# 07_USB_Type-C_DFP_DP_ALT.net
KiCad netlist of a schematic drawn in Altium Designer
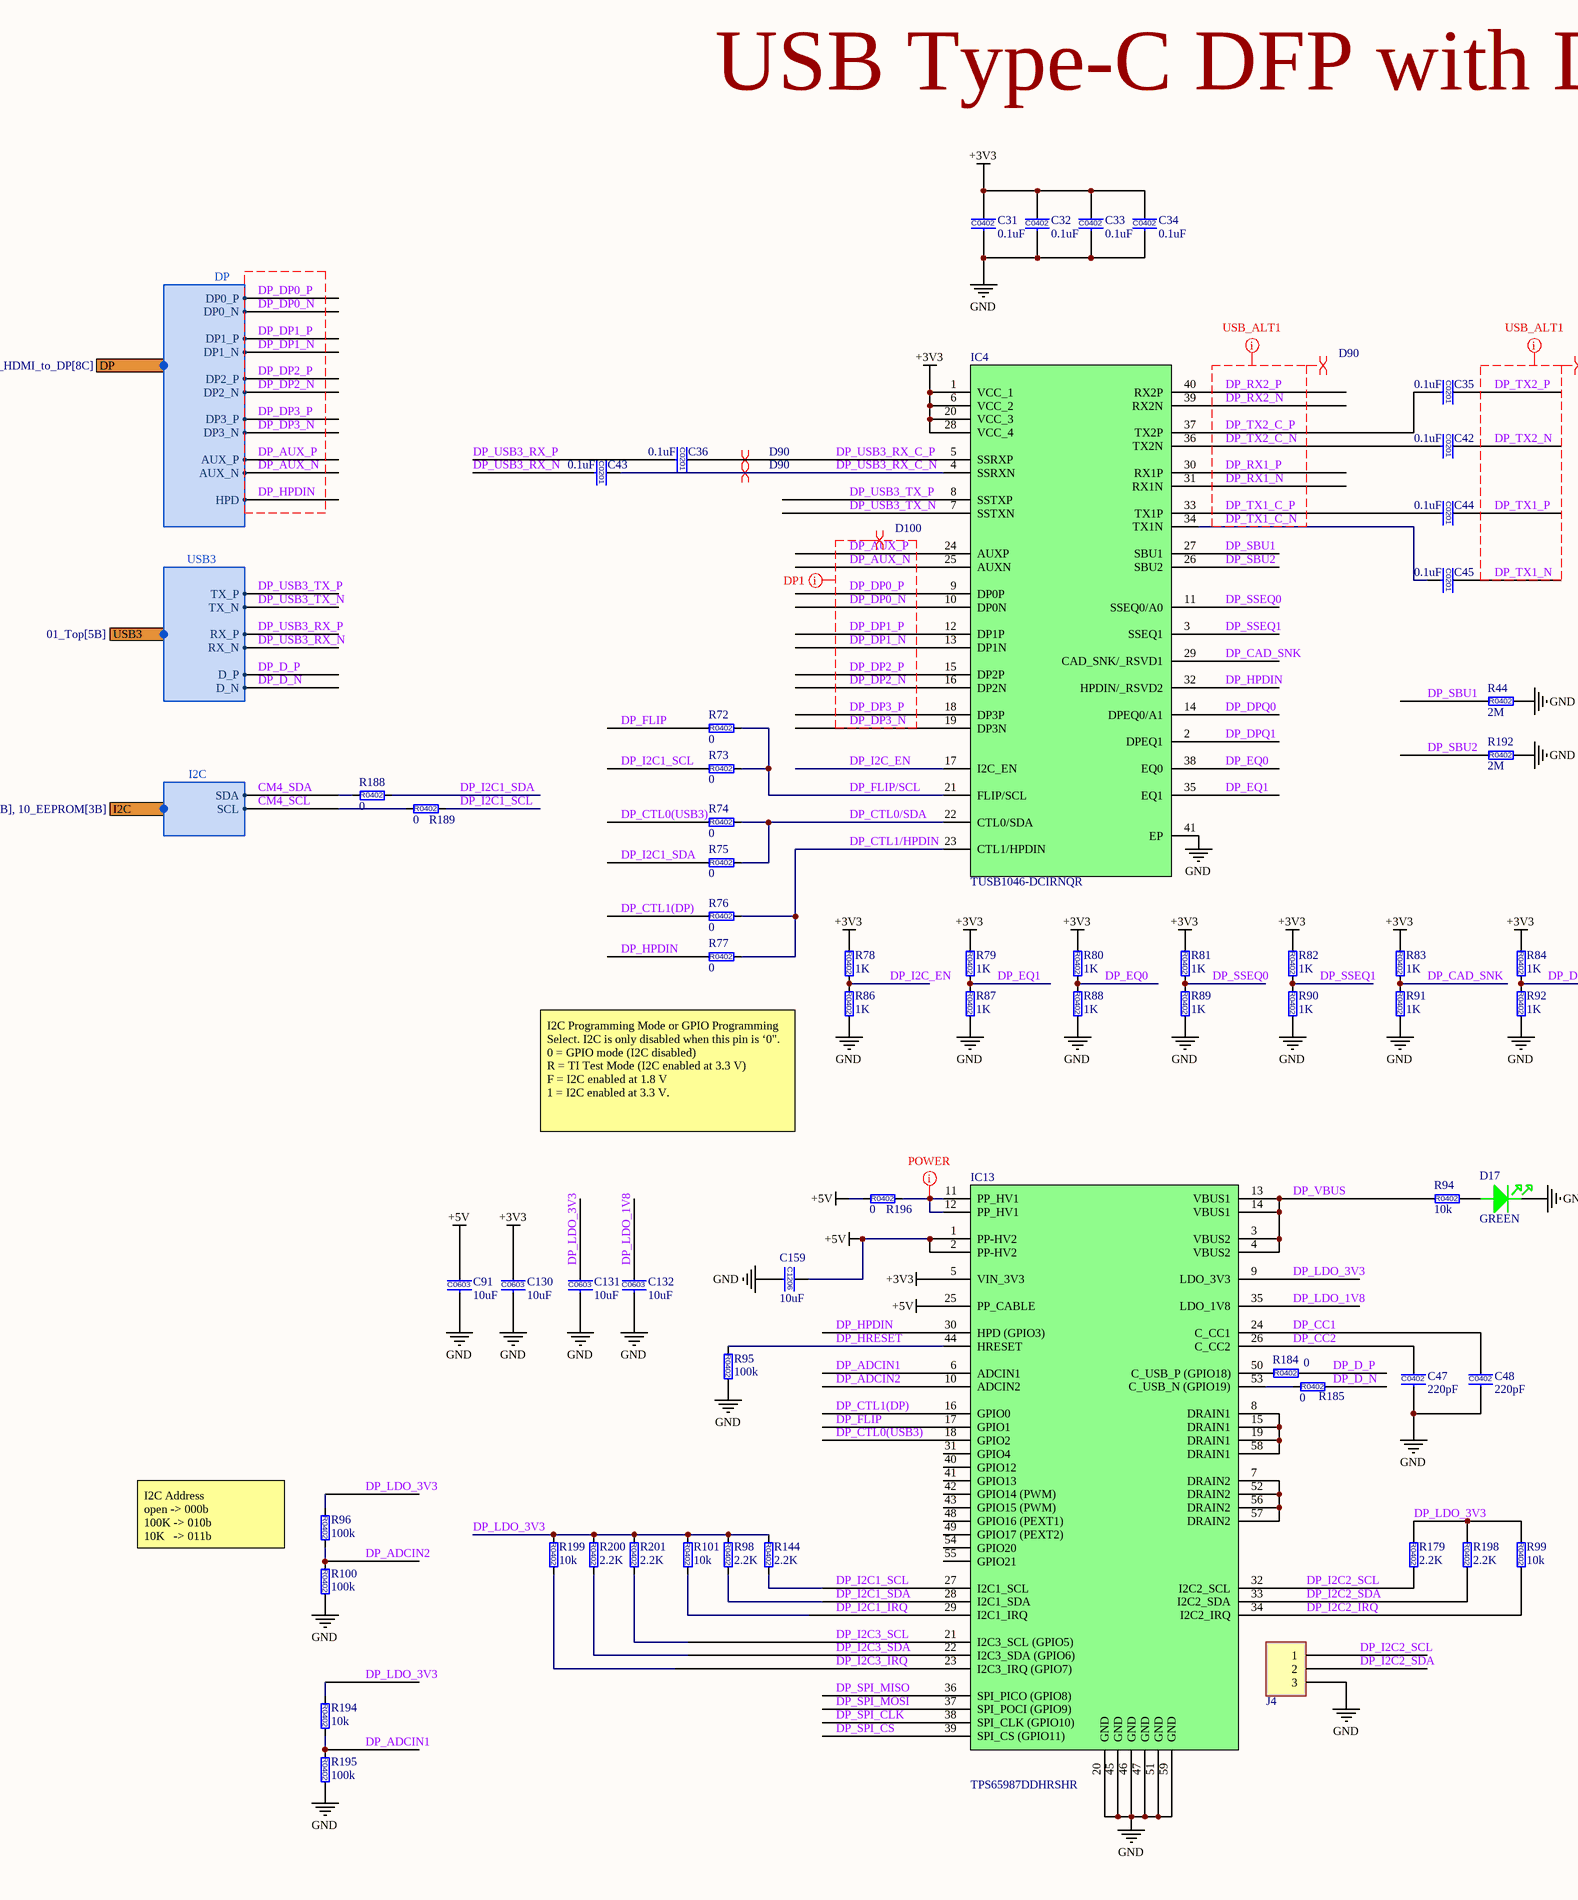
[diagram p0: 07_USB_Type-C_DFP_DP_ALT.SchDoc, left]
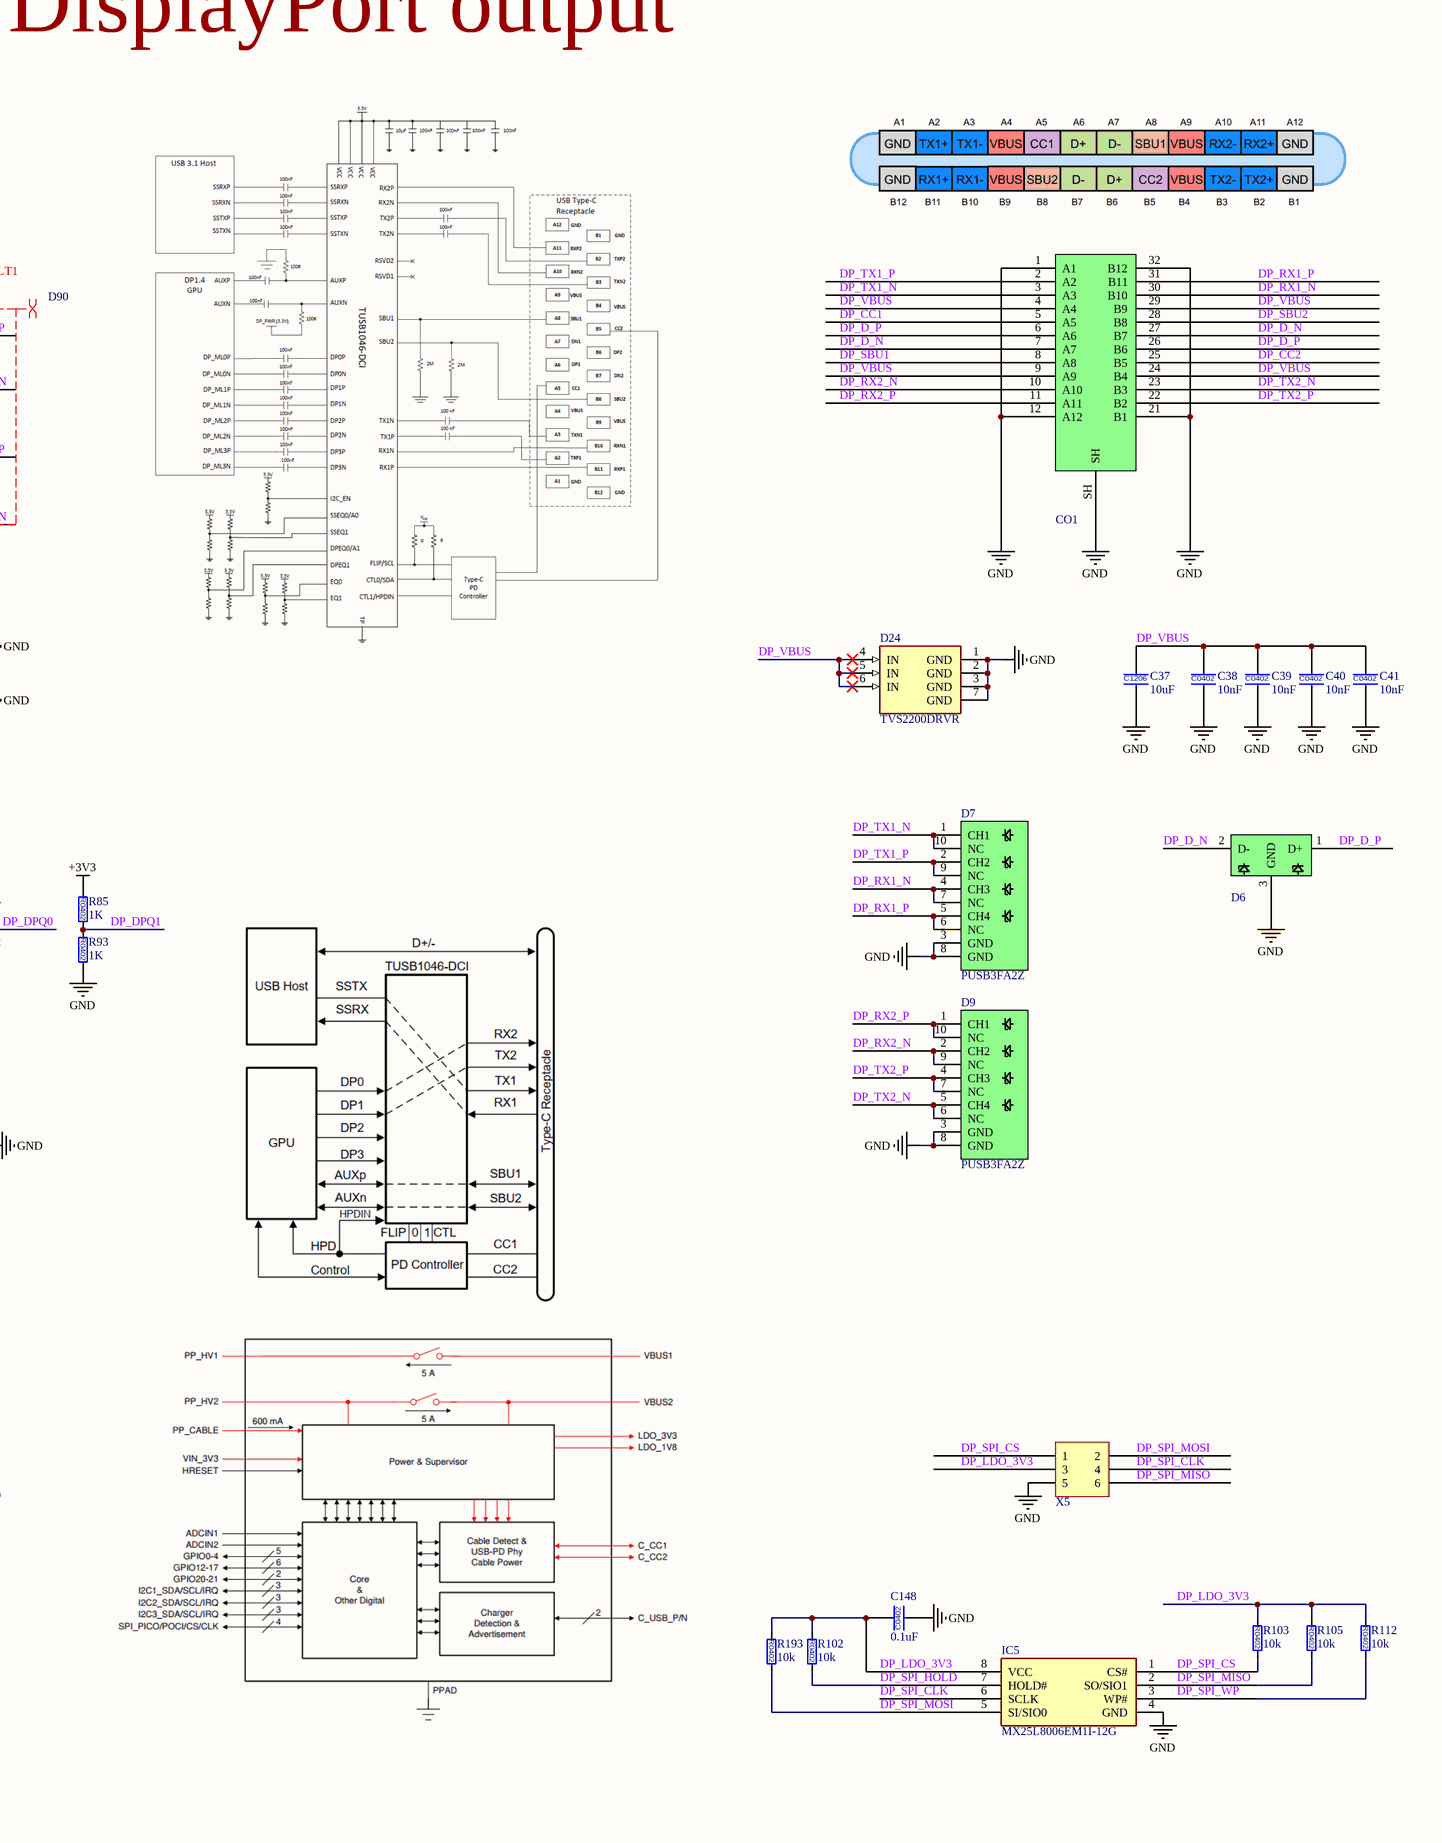
[diagram p1: 07_USB_Type-C_DFP_DP_ALT.SchDoc, right]

(export (version "E")
  (design (tool "Eeschema 10.0.6"))
  (components
    (comp (ref "C31")
      (value "0.1uF")
      (footprint "C0402")
      (description "CAP CER  0.1uF 10% 25V X5R 0402")
      (fields
        (field (name "MANUFACTURER") "AVX Corporation")
        (field (name "MANUFACTURER PART NUMBER") "04023D104KAT2A")
      )
      (libsource (lib "Capacitor") (part "04023D104KAT2A"))
    )
    (comp (ref "C32")
      (value "0.1uF")
      (footprint "C0402")
      (description "CAP CER  0.1uF 10% 25V X5R 0402")
      (fields
        (field (name "MANUFACTURER") "AVX Corporation")
        (field (name "MANUFACTURER PART NUMBER") "04023D104KAT2A")
      )
      (libsource (lib "Capacitor") (part "04023D104KAT2A"))
    )
    (comp (ref "C33")
      (value "0.1uF")
      (footprint "C0402")
      (description "CAP CER  0.1uF 10% 25V X5R 0402")
      (fields
        (field (name "MANUFACTURER") "AVX Corporation")
        (field (name "MANUFACTURER PART NUMBER") "04023D104KAT2A")
      )
      (libsource (lib "Capacitor") (part "04023D104KAT2A"))
    )
    (comp (ref "C34")
      (value "0.1uF")
      (footprint "C0402")
      (description "CAP CER  0.1uF 10% 25V X5R 0402")
      (fields
        (field (name "MANUFACTURER") "AVX Corporation")
        (field (name "MANUFACTURER PART NUMBER") "04023D104KAT2A")
      )
      (libsource (lib "Capacitor") (part "04023D104KAT2A"))
    )
    (comp (ref "C35")
      (value "0.1uF")
      (footprint "C0201")
      (description "CAP CER  0.1uF 10% 6.3V X5R 0201")
      (fields
        (field (name "MANUFACTURER") "AVX Corporation")
        (field (name "MANUFACTURER PART NUMBER") "02016D104KAT")
      )
      (libsource (lib "Capacitor") (part "02016D104KAT"))
    )
    (comp (ref "C36")
      (value "0.1uF")
      (footprint "C0201")
      (description "CAP CER  0.1uF 10% 6.3V X5R 0201")
      (fields
        (field (name "MANUFACTURER") "AVX Corporation")
        (field (name "MANUFACTURER PART NUMBER") "02016D104KAT")
      )
      (libsource (lib "Capacitor") (part "02016D104KAT"))
    )
    (comp (ref "C37")
      (value "10uF")
      (footprint "C1206")
      (description "CAP CER  10uF 10% 50V X5R 1206")
      (fields
        (field (name "MANUFACTURER") "KYOCERA AVX")
        (field (name "MANUFACTURER PART NUMBER") "12065D106KAT4A")
      )
      (libsource (lib "Capacitor") (part "12065D106KAT4A"))
    )
    (comp (ref "C38")
      (value "10nF")
      (footprint "C0402")
      (description "CAP CER 10nF 5% 50V X7R 0402")
      (fields
        (field (name "MANUFACTURER") "KYOCERA AVX")
        (field (name "MANUFACTURER PART NUMBER") "04025C103JAT2A")
      )
      (libsource (lib "Capacitor") (part "04025C103JAT2A"))
    )
    (comp (ref "C39")
      (value "10nF")
      (footprint "C0402")
      (description "CAP CER 10nF 5% 50V X7R 0402")
      (fields
        (field (name "MANUFACTURER") "KYOCERA AVX")
        (field (name "MANUFACTURER PART NUMBER") "04025C103JAT2A")
      )
      (libsource (lib "Capacitor") (part "04025C103JAT2A"))
    )
    (comp (ref "C40")
      (value "10nF")
      (footprint "C0402")
      (description "CAP CER 10nF 5% 50V X7R 0402")
      (fields
        (field (name "MANUFACTURER") "KYOCERA AVX")
        (field (name "MANUFACTURER PART NUMBER") "04025C103JAT2A")
      )
      (libsource (lib "Capacitor") (part "04025C103JAT2A"))
    )
    (comp (ref "C41")
      (value "10nF")
      (footprint "C0402")
      (description "CAP CER 10nF 5% 50V X7R 0402")
      (fields
        (field (name "MANUFACTURER") "KYOCERA AVX")
        (field (name "MANUFACTURER PART NUMBER") "04025C103JAT2A")
      )
      (libsource (lib "Capacitor") (part "04025C103JAT2A"))
    )
    (comp (ref "C42")
      (value "0.1uF")
      (footprint "C0201")
      (description "CAP CER  0.1uF 10% 6.3V X5R 0201")
      (fields
        (field (name "MANUFACTURER") "AVX Corporation")
        (field (name "MANUFACTURER PART NUMBER") "02016D104KAT")
      )
      (libsource (lib "Capacitor") (part "02016D104KAT"))
    )
    (comp (ref "C43")
      (value "0.1uF")
      (footprint "C0201")
      (description "CAP CER  0.1uF 10% 6.3V X5R 0201")
      (fields
        (field (name "MANUFACTURER") "AVX Corporation")
        (field (name "MANUFACTURER PART NUMBER") "02016D104KAT")
      )
      (libsource (lib "Capacitor") (part "02016D104KAT"))
    )
    (comp (ref "C44")
      (value "0.1uF")
      (footprint "C0201")
      (description "CAP CER  0.1uF 10% 6.3V X5R 0201")
      (fields
        (field (name "MANUFACTURER") "AVX Corporation")
        (field (name "MANUFACTURER PART NUMBER") "02016D104KAT")
      )
      (libsource (lib "Capacitor") (part "02016D104KAT"))
    )
    (comp (ref "C45")
      (value "0.1uF")
      (footprint "C0201")
      (description "CAP CER  0.1uF 10% 6.3V X5R 0201")
      (fields
        (field (name "MANUFACTURER") "AVX Corporation")
        (field (name "MANUFACTURER PART NUMBER") "02016D104KAT")
      )
      (libsource (lib "Capacitor") (part "02016D104KAT"))
    )
    (comp (ref "C47")
      (value "220pF")
      (footprint "C0402")
      (description "CAP CER  220pF 5% 25V NP0 0402")
      (fields
        (field (name "MANUFACTURER") "KYOCERA AVX")
        (field (name "MANUFACTURER PART NUMBER") "04023A221JAT4A")
      )
      (libsource (lib "Capacitor") (part "04023A221JAT4A"))
    )
    (comp (ref "C48")
      (value "220pF")
      (footprint "C0402")
      (description "CAP CER  220pF 5% 25V NP0 0402")
      (fields
        (field (name "MANUFACTURER") "KYOCERA AVX")
        (field (name "MANUFACTURER PART NUMBER") "04023A221JAT4A")
      )
      (libsource (lib "Capacitor") (part "04023A221JAT4A"))
    )
    (comp (ref "C91")
      (value "10uF")
      (footprint "C0603")
      (description "CAP CER 10uF 10% 10V X5R 0603")
      (fields
        (field (name "MANUFACTURER") "KYOCERA AVX")
        (field (name "MANUFACTURER PART NUMBER") "0603ZD106KAT2A")
      )
      (libsource (lib "Capacitor") (part "0603ZD106KAT2A"))
    )
    (comp (ref "C130")
      (value "10uF")
      (footprint "C0603")
      (description "CAP CER 10uF 10% 10V X5R 0603")
      (fields
        (field (name "MANUFACTURER") "KYOCERA AVX")
        (field (name "MANUFACTURER PART NUMBER") "0603ZD106KAT2A")
      )
      (libsource (lib "Capacitor") (part "0603ZD106KAT2A"))
    )
    (comp (ref "C131")
      (value "10uF")
      (footprint "C0603")
      (description "CAP CER 10uF 10% 10V X5R 0603")
      (fields
        (field (name "MANUFACTURER") "KYOCERA AVX")
        (field (name "MANUFACTURER PART NUMBER") "0603ZD106KAT2A")
      )
      (libsource (lib "Capacitor") (part "0603ZD106KAT2A"))
    )
    (comp (ref "C132")
      (value "10uF")
      (footprint "C0603")
      (description "CAP CER 10uF 10% 10V X5R 0603")
      (fields
        (field (name "MANUFACTURER") "KYOCERA AVX")
        (field (name "MANUFACTURER PART NUMBER") "0603ZD106KAT2A")
      )
      (libsource (lib "Capacitor") (part "0603ZD106KAT2A"))
    )
    (comp (ref "C148")
      (value "0.1uF")
      (footprint "C0402")
      (description "CAP CER  0.1uF 10% 25V X5R 0402")
      (fields
        (field (name "MANUFACTURER") "AVX Corporation")
        (field (name "MANUFACTURER PART NUMBER") "04023D104KAT2A")
      )
      (libsource (lib "Capacitor") (part "04023D104KAT2A"))
    )
    (comp (ref "C159")
      (value "10uF")
      (footprint "C1206")
      (description "CAP CER  10uF 10% 50V X5R 1206")
      (fields
        (field (name "MANUFACTURER") "KYOCERA AVX")
        (field (name "MANUFACTURER PART NUMBER") "12065D106KAT4A")
      )
      (libsource (lib "Capacitor") (part "12065D106KAT4A"))
    )
    (comp (ref "CO1")
      (value "USB4070-30-C")
      (footprint "USB4070-30-C")
      (description "24 Position 20 VDC USB Type C Horizontal USB 3.1 Receptacle Connector")
      (fields
        (field (name "PART NUMBER") "CO0021")
        (field (name "MANUFACTURER") "Global Connector Technology")
      )
      (libsource (lib "new") (part "USB4070-30-C"))
    )
    (comp (ref "D6")
      (value "TPD2EUSB30DRTR")
      (footprint "TPD2EUSB30DRTR_SOT-3")
      (fields (field (name "MANUFACTURER") "Texas Instruments"))
      (libsource (lib "new") (part "TPD2EUSB30DRTR"))
    )
    (comp (ref "D7")
      (value "PUSB3FA2Z")
      (footprint "PUSB3FA2Z_DFN_2510_10")
      (description "PUSB3FA2/SOT1176/XSON10")
      (fields (field (name "PART NUMBER") "DI0007") (field (name "MANUFACTURER") "Nexperia"))
      (libsource (lib "new") (part "PUSB3FA2Z"))
    )
    (comp (ref "D9")
      (value "PUSB3FA2Z")
      (footprint "PUSB3FA2Z_DFN_2510_10")
      (description "PUSB3FA2/SOT1176/XSON10")
      (fields (field (name "PART NUMBER") "DI0007") (field (name "MANUFACTURER") "Nexperia"))
      (libsource (lib "new") (part "PUSB3FA2Z"))
    )
    (comp (ref "D17")
      (value "GREEN")
      (footprint "LED_0603")
      (description "LED Uni-Color Yellow Green 574nm 2-Pin Chip 0603(1608Metric) T/R")
      (fields
        (field (name "MANUFACTURER") "Vishay Semiconductors")
        (field (name "MANUFACTURER PART NUMBER") "VLMG1300-GS08")
      )
      (libsource (lib "led") (part "LED_SMD_0603_GREEN"))
    )
    (comp (ref "D24")
      (value "TVS2200DRVR")
      (footprint "TVS2200D_SON_6")
      (description "22-V flat-clamp surge protection device 6-WSON -40 to 125")
      (fields
        (field (name "OCTOPART") "https://octopart.com/tvs2200drvr-texas+instruments-88217346")
        (field (name "MANUFACTURER") "Texas Instruments")
      )
      (libsource (lib "new") (part "TVS2200DRVR"))
    )
    (comp (ref "IC4")
      (value "TUSB1046-DCIRNQR")
      (footprint "TUSB1046_WQFN_40")
      (fields
        (field (name "MOUSER PART NUMBER") "595-TUSB1046-DCIRNQR")
        (field (name "MANUFACTURER") "Texas Instruments")
        (field (name "MANUFACTURER PART NUMBER") "TUSB1046AI-DCIRNQR")
      )
      (libsource (lib "new") (part "TUSB1046-DCIRNQR"))
    )
    (comp (ref "IC5")
      (value "MX25L8006EM1I-12G")
      (footprint "SamacSys:SOIC127P600X175-8N")
      (description "NOR Flash Serial 3.3V 8M-bit 8M/4M x 1/2-bit 8ns 8-Pin SOP / IC FLASH 8MBIT 86MHZ 8SOP")
      (fields (field (name "MANUFACTURER") "Macronix"))
      (libsource (lib "new") (part "MX25L8006EM1I-12G"))
    )
    (comp (ref "IC13")
      (value "TPS65987DDHRSHR")
      (footprint "TPS65987D_VQFN-56")
      (description "USB Type-C™ and USB PD controller with integrated power switches 56-VQFN -10 to 75")
      (fields (field (name "PART NUMBER") "IC0052") (field (name "MANUFACTURER") "Texas Instruments"))
      (libsource (lib "new") (part "TPS65987DDHRSHR"))
    )
    (comp (ref "J4")
      (value "PLS-3")
      (footprint "PLS-3-3D")
      (description "Board to Board Connector Straight Header Single Row 3 Position 2.54mm Pitch Through Hole Bag")
      (fields
        (field (name "MANUFACTURER") "Amphenol")
        (field (name "MANUFACTURER PART NUMBER") "G800W305018EU")
      )
      (libsource (lib "Connector") (part "PLS-3"))
    )
    (comp (ref "R44")
      (value "2M")
      (footprint "R0402")
      (description "RES SMD 2M ohm 1% 1/16W R0402")
      (fields
        (field (name "MANUFACTURER") "Vishay")
        (field (name "MANUFACTURER PART NUMBER") "CRCW04022M00FKEDC")
      )
      (libsource (lib "Resistor") (part "CRCW04022M00FKEDC"))
    )
    (comp (ref "R72")
      (value "0")
      (footprint "R0402")
      (description "RES SMD 0 ohm 1/16W R0402")
      (fields
        (field (name "MANUFACTURER") "Vishay Dale")
        (field (name "MANUFACTURER PART NUMBER") "CRCW04020000Z0")
      )
      (libsource (lib "Resistor") (part "CRCW04020000Z0"))
    )
    (comp (ref "R73")
      (value "0")
      (footprint "R0402")
      (description "RES SMD 0 ohm 1/16W R0402")
      (fields
        (field (name "MANUFACTURER") "Vishay Dale")
        (field (name "MANUFACTURER PART NUMBER") "CRCW04020000Z0")
      )
      (libsource (lib "Resistor") (part "CRCW04020000Z0"))
    )
    (comp (ref "R74")
      (value "0")
      (footprint "R0402")
      (description "RES SMD 0 ohm 1/16W R0402")
      (fields
        (field (name "MANUFACTURER") "Vishay Dale")
        (field (name "MANUFACTURER PART NUMBER") "CRCW04020000Z0")
      )
      (libsource (lib "Resistor") (part "CRCW04020000Z0"))
    )
    (comp (ref "R75")
      (value "0")
      (footprint "R0402")
      (description "RES SMD 0 ohm 1/16W R0402")
      (fields
        (field (name "MANUFACTURER") "Vishay Dale")
        (field (name "MANUFACTURER PART NUMBER") "CRCW04020000Z0")
      )
      (libsource (lib "Resistor") (part "CRCW04020000Z0"))
    )
    (comp (ref "R76")
      (value "0")
      (footprint "R0402")
      (description "RES SMD 0 ohm 1/16W R0402")
      (fields
        (field (name "MANUFACTURER") "Vishay Dale")
        (field (name "MANUFACTURER PART NUMBER") "CRCW04020000Z0")
      )
      (libsource (lib "Resistor") (part "CRCW04020000Z0"))
    )
    (comp (ref "R77")
      (value "0")
      (footprint "R0402")
      (description "RES SMD 0 ohm 1/16W R0402")
      (fields
        (field (name "MANUFACTURER") "Vishay Dale")
        (field (name "MANUFACTURER PART NUMBER") "CRCW04020000Z0")
      )
      (libsource (lib "Resistor") (part "CRCW04020000Z0"))
    )
    (comp (ref "R78")
      (value "1K")
      (footprint "R0402")
      (description "RES SMD 1K ohm 1% 1/16W R0402")
      (fields
        (field (name "MANUFACTURER") "Vishay")
        (field (name "MANUFACTURER PART NUMBER") "CRCW04021K00FKEDC")
      )
      (libsource (lib "Resistor") (part "CRCW04021K00FKEDC"))
    )
    (comp (ref "R79")
      (value "1K")
      (footprint "R0402")
      (description "RES SMD 1K ohm 1% 1/16W R0402")
      (fields
        (field (name "MANUFACTURER") "Vishay")
        (field (name "MANUFACTURER PART NUMBER") "CRCW04021K00FKEDC")
      )
      (libsource (lib "Resistor") (part "CRCW04021K00FKEDC"))
    )
    (comp (ref "R80")
      (value "1K")
      (footprint "R0402")
      (description "RES SMD 1K ohm 1% 1/16W R0402")
      (fields
        (field (name "MANUFACTURER") "Vishay")
        (field (name "MANUFACTURER PART NUMBER") "CRCW04021K00FKEDC")
      )
      (libsource (lib "Resistor") (part "CRCW04021K00FKEDC"))
    )
    (comp (ref "R81")
      (value "1K")
      (footprint "R0402")
      (description "RES SMD 1K ohm 1% 1/16W R0402")
      (fields
        (field (name "MANUFACTURER") "Vishay")
        (field (name "MANUFACTURER PART NUMBER") "CRCW04021K00FKEDC")
      )
      (libsource (lib "Resistor") (part "CRCW04021K00FKEDC"))
    )
    (comp (ref "R82")
      (value "1K")
      (footprint "R0402")
      (description "RES SMD 1K ohm 1% 1/16W R0402")
      (fields
        (field (name "MANUFACTURER") "Vishay")
        (field (name "MANUFACTURER PART NUMBER") "CRCW04021K00FKEDC")
      )
      (libsource (lib "Resistor") (part "CRCW04021K00FKEDC"))
    )
    (comp (ref "R83")
      (value "1K")
      (footprint "R0402")
      (description "RES SMD 1K ohm 1% 1/16W R0402")
      (fields
        (field (name "MANUFACTURER") "Vishay")
        (field (name "MANUFACTURER PART NUMBER") "CRCW04021K00FKEDC")
      )
      (libsource (lib "Resistor") (part "CRCW04021K00FKEDC"))
    )
    (comp (ref "R84")
      (value "1K")
      (footprint "R0402")
      (description "RES SMD 1K ohm 1% 1/16W R0402")
      (fields
        (field (name "MANUFACTURER") "Vishay")
        (field (name "MANUFACTURER PART NUMBER") "CRCW04021K00FKEDC")
      )
      (libsource (lib "Resistor") (part "CRCW04021K00FKEDC"))
    )
    (comp (ref "R85")
      (value "1K")
      (footprint "R0402")
      (description "RES SMD 1K ohm 1% 1/16W R0402")
      (fields
        (field (name "MANUFACTURER") "Vishay")
        (field (name "MANUFACTURER PART NUMBER") "CRCW04021K00FKEDC")
      )
      (libsource (lib "Resistor") (part "CRCW04021K00FKEDC"))
    )
    (comp (ref "R86")
      (value "1K")
      (footprint "R0402")
      (description "RES SMD 1K ohm 1% 1/16W R0402")
      (fields
        (field (name "MANUFACTURER") "Vishay")
        (field (name "MANUFACTURER PART NUMBER") "CRCW04021K00FKEDC")
      )
      (libsource (lib "Resistor") (part "CRCW04021K00FKEDC"))
    )
    (comp (ref "R87")
      (value "1K")
      (footprint "R0402")
      (description "RES SMD 1K ohm 1% 1/16W R0402")
      (fields
        (field (name "MANUFACTURER") "Vishay")
        (field (name "MANUFACTURER PART NUMBER") "CRCW04021K00FKEDC")
      )
      (libsource (lib "Resistor") (part "CRCW04021K00FKEDC"))
    )
    (comp (ref "R88")
      (value "1K")
      (footprint "R0402")
      (description "RES SMD 1K ohm 1% 1/16W R0402")
      (fields
        (field (name "MANUFACTURER") "Vishay")
        (field (name "MANUFACTURER PART NUMBER") "CRCW04021K00FKEDC")
      )
      (libsource (lib "Resistor") (part "CRCW04021K00FKEDC"))
    )
    (comp (ref "R89")
      (value "1K")
      (footprint "R0402")
      (description "RES SMD 1K ohm 1% 1/16W R0402")
      (fields
        (field (name "MANUFACTURER") "Vishay")
        (field (name "MANUFACTURER PART NUMBER") "CRCW04021K00FKEDC")
      )
      (libsource (lib "Resistor") (part "CRCW04021K00FKEDC"))
    )
    (comp (ref "R90")
      (value "1K")
      (footprint "R0402")
      (description "RES SMD 1K ohm 1% 1/16W R0402")
      (fields
        (field (name "MANUFACTURER") "Vishay")
        (field (name "MANUFACTURER PART NUMBER") "CRCW04021K00FKEDC")
      )
      (libsource (lib "Resistor") (part "CRCW04021K00FKEDC"))
    )
    (comp (ref "R91")
      (value "1K")
      (footprint "R0402")
      (description "RES SMD 1K ohm 1% 1/16W R0402")
      (fields
        (field (name "MANUFACTURER") "Vishay")
        (field (name "MANUFACTURER PART NUMBER") "CRCW04021K00FKEDC")
      )
      (libsource (lib "Resistor") (part "CRCW04021K00FKEDC"))
    )
    (comp (ref "R92")
      (value "1K")
      (footprint "R0402")
      (description "RES SMD 1K ohm 1% 1/16W R0402")
      (fields
        (field (name "MANUFACTURER") "Vishay")
        (field (name "MANUFACTURER PART NUMBER") "CRCW04021K00FKEDC")
      )
      (libsource (lib "Resistor") (part "CRCW04021K00FKEDC"))
    )
    (comp (ref "R93")
      (value "1K")
      (footprint "R0402")
      (description "RES SMD 1K ohm 1% 1/16W R0402")
      (fields
        (field (name "MANUFACTURER") "Vishay")
        (field (name "MANUFACTURER PART NUMBER") "CRCW04021K00FKEDC")
      )
      (libsource (lib "Resistor") (part "CRCW04021K00FKEDC"))
    )
    (comp (ref "R94")
      (value "10k")
      (footprint "R0402")
      (description "RES SMD 10K ohm 1% 1/16W R0402")
      (fields
        (field (name "MANUFACTURER") "Vishay")
        (field (name "MANUFACTURER PART NUMBER") "CRCW040210K0FK")
      )
      (libsource (lib "Resistor") (part "CRCW040210K0FK"))
    )
    (comp (ref "R95")
      (value "100k")
      (footprint "R0402")
      (description "RES SMD 100K ohm 1% 1/16W R0402")
      (fields
        (field (name "MANUFACTURER") "Vishay")
        (field (name "MANUFACTURER PART NUMBER") "CRCW0402100KFKEDC")
      )
      (libsource (lib "Resistor") (part "CRCW0402100KFKEDC"))
    )
    (comp (ref "R96")
      (value "100k")
      (footprint "R0402")
      (description "RES SMD 100K ohm 1% 1/16W R0402")
      (fields
        (field (name "MANUFACTURER") "Vishay")
        (field (name "MANUFACTURER PART NUMBER") "CRCW0402100KFKEDC")
      )
      (libsource (lib "Resistor") (part "CRCW0402100KFKEDC"))
    )
    (comp (ref "R98")
      (value "2.2K")
      (footprint "R0402")
      (description "RES SMD 2.2K ohm 1% 1/16W R0402")
      (fields
        (field (name "MANUFACTURER") "Vishay")
        (field (name "MANUFACTURER PART NUMBER") "CRCW04022K20FK")
      )
      (libsource (lib "Resistor") (part "CRCW04022K20FK"))
    )
    (comp (ref "R99")
      (value "10k")
      (footprint "R0402")
      (description "RES SMD 10K ohm 1% 1/16W R0402")
      (fields
        (field (name "MANUFACTURER") "Vishay")
        (field (name "MANUFACTURER PART NUMBER") "CRCW040210K0FK")
      )
      (libsource (lib "Resistor") (part "CRCW040210K0FK"))
    )
    (comp (ref "R100")
      (value "100k")
      (footprint "R0402")
      (description "RES SMD 100K ohm 1% 1/16W R0402")
      (fields
        (field (name "MANUFACTURER") "Vishay")
        (field (name "MANUFACTURER PART NUMBER") "CRCW0402100KFKEDC")
      )
      (libsource (lib "Resistor") (part "CRCW0402100KFKEDC"))
    )
    (comp (ref "R101")
      (value "10k")
      (footprint "R0402")
      (description "RES SMD 10K ohm 1% 1/16W R0402")
      (fields
        (field (name "MANUFACTURER") "Vishay")
        (field (name "MANUFACTURER PART NUMBER") "CRCW040210K0FK")
      )
      (libsource (lib "Resistor") (part "CRCW040210K0FK"))
    )
    (comp (ref "R102")
      (value "10k")
      (footprint "R0402")
      (description "RES SMD 10K ohm 1% 1/16W R0402")
      (fields
        (field (name "MANUFACTURER") "Vishay Dale")
        (field (name "MANUFACTURER PART NUMBER") "CRCW040210K0FK")
      )
      (libsource (lib "Resistor") (part "CRCW040210K0FK"))
    )
    (comp (ref "R103")
      (value "10k")
      (footprint "R0402")
      (description "RES SMD 10K ohm 1% 1/16W R0402")
      (fields
        (field (name "MANUFACTURER") "Vishay Dale")
        (field (name "MANUFACTURER PART NUMBER") "CRCW040210K0FK")
      )
      (libsource (lib "Resistor") (part "CRCW040210K0FK"))
    )
    (comp (ref "R105")
      (value "10k")
      (footprint "R0402")
      (description "RES SMD 10K ohm 1% 1/16W R0402")
      (fields
        (field (name "MANUFACTURER") "Vishay Dale")
        (field (name "MANUFACTURER PART NUMBER") "CRCW040210K0FK")
      )
      (libsource (lib "Resistor") (part "CRCW040210K0FK"))
    )
    (comp (ref "R112")
      (value "10k")
      (footprint "R0402")
      (description "RES SMD 10K ohm 1% 1/16W R0402")
      (fields
        (field (name "MANUFACTURER") "Vishay Dale")
        (field (name "MANUFACTURER PART NUMBER") "CRCW040210K0FK")
      )
      (libsource (lib "Resistor") (part "CRCW040210K0FK"))
    )
    (comp (ref "R144")
      (value "2.2K")
      (footprint "R0402")
      (description "RES SMD 2.2K ohm 1% 1/16W R0402")
      (fields
        (field (name "MANUFACTURER") "Vishay")
        (field (name "MANUFACTURER PART NUMBER") "CRCW04022K20FK")
      )
      (libsource (lib "Resistor") (part "CRCW04022K20FK"))
    )
    (comp (ref "R179")
      (value "2.2K")
      (footprint "R0402")
      (description "RES SMD 2.2K ohm 1% 1/16W R0402")
      (fields
        (field (name "MANUFACTURER") "Vishay")
        (field (name "MANUFACTURER PART NUMBER") "CRCW04022K20FK")
      )
      (libsource (lib "Resistor") (part "CRCW04022K20FK"))
    )
    (comp (ref "R184")
      (value "0")
      (footprint "R0402")
      (description "RES SMD 0 ohm 1/16W R0402")
      (fields
        (field (name "MANUFACTURER") "Vishay Dale")
        (field (name "MANUFACTURER PART NUMBER") "CRCW04020000Z0")
      )
      (libsource (lib "Resistor") (part "CRCW04020000Z0"))
    )
    (comp (ref "R185")
      (value "0")
      (footprint "R0402")
      (description "RES SMD 0 ohm 1/16W R0402")
      (fields
        (field (name "MANUFACTURER") "Vishay Dale")
        (field (name "MANUFACTURER PART NUMBER") "CRCW04020000Z0")
      )
      (libsource (lib "Resistor") (part "CRCW04020000Z0"))
    )
    (comp (ref "R188")
      (value "0")
      (footprint "R0402")
      (description "RES SMD 0 ohm 1/16W R0402")
      (fields
        (field (name "MANUFACTURER") "Vishay Dale")
        (field (name "MANUFACTURER PART NUMBER") "CRCW04020000Z0")
      )
      (libsource (lib "Resistor") (part "CRCW04020000Z0"))
    )
    (comp (ref "R189")
      (value "0")
      (footprint "R0402")
      (description "RES SMD 0 ohm 1/16W R0402")
      (fields
        (field (name "MANUFACTURER") "Vishay Dale")
        (field (name "MANUFACTURER PART NUMBER") "CRCW04020000Z0")
      )
      (libsource (lib "Resistor") (part "CRCW04020000Z0"))
    )
    (comp (ref "R192")
      (value "2M")
      (footprint "R0402")
      (description "RES SMD 2M ohm 1% 1/16W R0402")
      (fields
        (field (name "MANUFACTURER") "Vishay")
        (field (name "MANUFACTURER PART NUMBER") "CRCW04022M00FKEDC")
      )
      (libsource (lib "Resistor") (part "CRCW04022M00FKEDC"))
    )
    (comp (ref "R193")
      (value "10k")
      (footprint "R0402")
      (description "RES SMD 10K ohm 1% 1/16W R0402")
      (fields
        (field (name "MANUFACTURER") "Vishay Dale")
        (field (name "MANUFACTURER PART NUMBER") "CRCW040210K0FK")
      )
      (libsource (lib "Resistor") (part "CRCW040210K0FK"))
    )
    (comp (ref "R194")
      (value "10k")
      (footprint "R0402")
      (description "RES SMD 10K ohm 1% 1/16W R0402")
      (fields
        (field (name "MANUFACTURER") "Vishay")
        (field (name "MANUFACTURER PART NUMBER") "CRCW040210K0FK")
      )
      (libsource (lib "Resistor") (part "CRCW040210K0FK"))
    )
    (comp (ref "R195")
      (value "100k")
      (footprint "R0402")
      (description "RES SMD 100K ohm 1% 1/16W R0402")
      (fields
        (field (name "MANUFACTURER") "Vishay")
        (field (name "MANUFACTURER PART NUMBER") "CRCW0402100KFKEDC")
      )
      (libsource (lib "Resistor") (part "CRCW0402100KFKEDC"))
    )
    (comp (ref "R196")
      (value "0")
      (footprint "R0402")
      (description "RES SMD 0 ohm 1/16W R0402")
      (fields
        (field (name "MANUFACTURER") "Vishay Dale")
        (field (name "MANUFACTURER PART NUMBER") "CRCW04020000Z0")
      )
      (libsource (lib "Resistor") (part "CRCW04020000Z0"))
    )
    (comp (ref "R198")
      (value "2.2K")
      (footprint "R0402")
      (description "RES SMD 2.2K ohm 1% 1/16W R0402")
      (fields
        (field (name "MANUFACTURER") "Vishay")
        (field (name "MANUFACTURER PART NUMBER") "CRCW04022K20FK")
      )
      (libsource (lib "Resistor") (part "CRCW04022K20FK"))
    )
    (comp (ref "R199")
      (value "10k")
      (footprint "R0402")
      (description "RES SMD 10K ohm 1% 1/16W R0402")
      (fields
        (field (name "MANUFACTURER") "Vishay")
        (field (name "MANUFACTURER PART NUMBER") "CRCW040210K0FK")
      )
      (libsource (lib "Resistor") (part "CRCW040210K0FK"))
    )
    (comp (ref "R200")
      (value "2.2K")
      (footprint "R0402")
      (description "RES SMD 2.2K ohm 1% 1/16W R0402")
      (fields
        (field (name "MANUFACTURER") "Vishay")
        (field (name "MANUFACTURER PART NUMBER") "CRCW04022K20FK")
      )
      (libsource (lib "Resistor") (part "CRCW04022K20FK"))
    )
    (comp (ref "R201")
      (value "2.2K")
      (footprint "R0402")
      (description "RES SMD 2.2K ohm 1% 1/16W R0402")
      (fields
        (field (name "MANUFACTURER") "Vishay")
        (field (name "MANUFACTURER PART NUMBER") "CRCW04022K20FK")
      )
      (libsource (lib "Resistor") (part "CRCW04022K20FK"))
    )
    (comp (ref "X5")
      (value "PBD-6")
      (footprint "PXD-6")
      (description "Conn Unshrouded Header HDR 6 POS 2.54mm Solder ST Thru-Hole Poly Bag")
      (fields
        (field (name "MANUFACTURER") "Amphenol ICC / FCI")
        (field (name "MANUFACTURER PART NUMBER") "10076801-101-06LF")
        (field (name "PUBLISHER") "Altium Limited")
      )
      (libsource (lib "Connector") (part "PBD-6"))
    )
  )
  (nets
    (net (code "4") (name "+3V3") (class "Default")
      (node (ref "C130") (pin "1") (pinfunction "1_1") (pintype "passive"))
      (node (ref "C31") (pin "1") (pinfunction "1_1") (pintype "passive"))
      (node (ref "C32") (pin "1") (pinfunction "1_1") (pintype "passive"))
      (node (ref "C33") (pin "1") (pinfunction "1_1") (pintype "passive"))
      (node (ref "C34") (pin "1") (pinfunction "1_1") (pintype "passive"))
      (node (ref "IC13") (pin "5") (pinfunction "VIN_3V3_5") (pintype "passive"))
      (node (ref "IC4") (pin "1") (pinfunction "VCC_1_1") (pintype "passive"))
      (node (ref "IC4") (pin "20") (pinfunction "VCC_3_20") (pintype "passive"))
      (node (ref "IC4") (pin "28") (pinfunction "VCC_4_28") (pintype "passive"))
      (node (ref "IC4") (pin "6") (pinfunction "VCC_2_6") (pintype "passive"))
      (node (ref "R78") (pin "1") (pinfunction "1_1") (pintype "passive"))
      (node (ref "R79") (pin "1") (pinfunction "1_1") (pintype "passive"))
      (node (ref "R80") (pin "1") (pinfunction "1_1") (pintype "passive"))
      (node (ref "R81") (pin "1") (pinfunction "1_1") (pintype "passive"))
      (node (ref "R82") (pin "1") (pinfunction "1_1") (pintype "passive"))
      (node (ref "R83") (pin "1") (pinfunction "1_1") (pintype "passive"))
      (node (ref "R84") (pin "1") (pinfunction "1_1") (pintype "passive"))
      (node (ref "R85") (pin "1") (pinfunction "1_1") (pintype "passive"))
    )
    (net (code "5") (name "+5V") (class "Default")
      (node (ref "C159") (pin "1") (pinfunction "1_1") (pintype "passive"))
      (node (ref "C91") (pin "1") (pinfunction "1_1") (pintype "passive"))
      (node (ref "IC13") (pin "1") (pinfunction "PP-HV2_1") (pintype "passive"))
      (node (ref "IC13") (pin "2") (pinfunction "PP-HV2_2") (pintype "passive"))
      (node (ref "IC13") (pin "25") (pinfunction "PP_CABLE_25") (pintype "passive"))
      (node (ref "R196") (pin "1") (pinfunction "1_1") (pintype "passive"))
    )
    (net (code "6") (name "/CM4_SCL") (class "Default")
      (node (ref "R189") (pin "1") (pinfunction "1_1") (pintype "passive"))
    )
    (net (code "7") (name "/CM4_SDA") (class "Default")
      (node (ref "R188") (pin "1") (pinfunction "1_1") (pintype "passive"))
    )
    (net (code "8") (name "/DP_ADCIN1") (class "Default")
      (node (ref "IC13") (pin "6") (pinfunction "ADCIN1_6") (pintype "passive"))
      (node (ref "R194") (pin "2") (pinfunction "2_2") (pintype "passive"))
      (node (ref "R195") (pin "1") (pinfunction "1_1") (pintype "passive"))
    )
    (net (code "9") (name "/DP_ADCIN2") (class "Default")
      (node (ref "IC13") (pin "10") (pinfunction "ADCIN2_10") (pintype "passive"))
      (node (ref "R100") (pin "1") (pinfunction "1_1") (pintype "passive"))
      (node (ref "R96") (pin "2") (pinfunction "2_2") (pintype "passive"))
    )
    (net (code "10") (name "/DP_AUX_N") (class "Default")
      (node (ref "IC4") (pin "25") (pinfunction "AUXN_25") (pintype "passive"))
    )
    (net (code "11") (name "/DP_AUX_P") (class "Default")
      (node (ref "IC4") (pin "24") (pinfunction "AUXP_24") (pintype "passive"))
    )
    (net (code "12") (name "/DP_CAD_SNK") (class "Default")
      (node (ref "IC4") (pin "29") (pinfunction "CAD_SNK/_RSVD1_29") (pintype "passive"))
      (node (ref "R83") (pin "2") (pinfunction "2_2") (pintype "passive"))
      (node (ref "R91") (pin "1") (pinfunction "1_1") (pintype "passive"))
    )
    (net (code "13") (name "/DP_CC1") (class "Default")
      (node (ref "C48") (pin "1") (pinfunction "1_1") (pintype "passive"))
      (node (ref "CO1") (pin "5") (pinfunction "A5_5") (pintype "passive"))
      (node (ref "IC13") (pin "24") (pinfunction "C_CC1_24") (pintype "passive"))
    )
    (net (code "14") (name "/DP_CC2") (class "Default")
      (node (ref "C47") (pin "1") (pinfunction "1_1") (pintype "passive"))
      (node (ref "CO1") (pin "25") (pinfunction "B5_25") (pintype "passive"))
      (node (ref "IC13") (pin "26") (pinfunction "C_CC2_26") (pintype "passive"))
    )
    (net (code "15") (name "/DP_CTL0(USB3)") (class "Default")
      (node (ref "IC13") (pin "18") (pinfunction "GPIO2_18") (pintype "passive"))
      (node (ref "R74") (pin "1") (pinfunction "1_1") (pintype "passive"))
    )
    (net (code "16") (name "/DP_CTL0{slash}SDA") (class "Default")
      (node (ref "IC4") (pin "22") (pinfunction "CTL0/SDA_22") (pintype "passive"))
      (node (ref "R74") (pin "2") (pinfunction "2_2") (pintype "passive"))
      (node (ref "R75") (pin "2") (pinfunction "2_2") (pintype "passive"))
    )
    (net (code "17") (name "/DP_CTL1(DP)") (class "Default")
      (node (ref "IC13") (pin "16") (pinfunction "GPIO0_16") (pintype "passive"))
      (node (ref "R76") (pin "1") (pinfunction "1_1") (pintype "passive"))
    )
    (net (code "18") (name "/DP_CTL1{slash}HPDIN") (class "Default")
      (node (ref "IC4") (pin "23") (pinfunction "CTL1/HPDIN_23") (pintype "passive"))
      (node (ref "R76") (pin "2") (pinfunction "2_2") (pintype "passive"))
      (node (ref "R77") (pin "2") (pinfunction "2_2") (pintype "passive"))
    )
    (net (code "19") (name "/DP_DP0_N") (class "Default")
      (node (ref "IC4") (pin "10") (pinfunction "DP0N_10") (pintype "passive"))
    )
    (net (code "20") (name "/DP_DP0_P") (class "Default")
      (node (ref "IC4") (pin "9") (pinfunction "DP0P_9") (pintype "passive"))
    )
    (net (code "21") (name "/DP_DP1_N") (class "Default")
      (node (ref "IC4") (pin "13") (pinfunction "DP1N_13") (pintype "passive"))
    )
    (net (code "22") (name "/DP_DP1_P") (class "Default")
      (node (ref "IC4") (pin "12") (pinfunction "DP1P_12") (pintype "passive"))
    )
    (net (code "23") (name "/DP_DP2_N") (class "Default")
      (node (ref "IC4") (pin "16") (pinfunction "DP2N_16") (pintype "passive"))
    )
    (net (code "24") (name "/DP_DP2_P") (class "Default")
      (node (ref "IC4") (pin "15") (pinfunction "DP2P_15") (pintype "passive"))
    )
    (net (code "25") (name "/DP_DP3_N") (class "Default")
      (node (ref "IC4") (pin "19") (pinfunction "DP3N_19") (pintype "passive"))
    )
    (net (code "26") (name "/DP_DP3_P") (class "Default")
      (node (ref "IC4") (pin "18") (pinfunction "DP3P_18") (pintype "passive"))
    )
    (net (code "27") (name "/DP_DPQ0") (class "Default")
      (node (ref "IC4") (pin "14") (pinfunction "DPEQ0/A1_14") (pintype "passive"))
      (node (ref "R84") (pin "2") (pinfunction "2_2") (pintype "passive"))
      (node (ref "R92") (pin "1") (pinfunction "1_1") (pintype "passive"))
    )
    (net (code "28") (name "/DP_DPQ1") (class "Default")
      (node (ref "IC4") (pin "2") (pinfunction "DPEQ1_2") (pintype "passive"))
      (node (ref "R85") (pin "2") (pinfunction "2_2") (pintype "passive"))
      (node (ref "R93") (pin "1") (pinfunction "1_1") (pintype "passive"))
    )
    (net (code "29") (name "/DP_D_N") (class "Default")
      (node (ref "CO1") (pin "27") (pinfunction "B7_27") (pintype "passive"))
      (node (ref "CO1") (pin "7") (pinfunction "A7_7") (pintype "passive"))
      (node (ref "D6") (pin "2") (pinfunction "D-_2") (pintype "passive"))
      (node (ref "R185") (pin "2") (pinfunction "2_2") (pintype "passive"))
    )
    (net (code "30") (name "/DP_D_P") (class "Default")
      (node (ref "CO1") (pin "26") (pinfunction "B6_26") (pintype "passive"))
      (node (ref "CO1") (pin "6") (pinfunction "A6_6") (pintype "passive"))
      (node (ref "D6") (pin "1") (pinfunction "D+_1") (pintype "passive"))
      (node (ref "R184") (pin "2") (pinfunction "2_2") (pintype "passive"))
    )
    (net (code "31") (name "/DP_EQ0") (class "Default")
      (node (ref "IC4") (pin "38") (pinfunction "EQ0_38") (pintype "passive"))
      (node (ref "R80") (pin "2") (pinfunction "2_2") (pintype "passive"))
      (node (ref "R88") (pin "1") (pinfunction "1_1") (pintype "passive"))
    )
    (net (code "32") (name "/DP_EQ1") (class "Default")
      (node (ref "IC4") (pin "35") (pinfunction "EQ1_35") (pintype "passive"))
      (node (ref "R79") (pin "2") (pinfunction "2_2") (pintype "passive"))
      (node (ref "R87") (pin "1") (pinfunction "1_1") (pintype "passive"))
    )
    (net (code "33") (name "/DP_FLIP") (class "Default")
      (node (ref "IC13") (pin "17") (pinfunction "GPIO1_17") (pintype "passive"))
      (node (ref "R72") (pin "1") (pinfunction "1_1") (pintype "passive"))
    )
    (net (code "34") (name "/DP_FLIP{slash}SCL") (class "Default")
      (node (ref "IC4") (pin "21") (pinfunction "FLIP/SCL_21") (pintype "passive"))
      (node (ref "R72") (pin "2") (pinfunction "2_2") (pintype "passive"))
      (node (ref "R73") (pin "2") (pinfunction "2_2") (pintype "passive"))
    )
    (net (code "35") (name "/DP_HPDIN") (class "Default")
      (node (ref "IC13") (pin "30") (pinfunction "HPD_(GPIO3)_30") (pintype "passive"))
      (node (ref "IC4") (pin "32") (pinfunction "HPDIN/_RSVD2_32") (pintype "passive"))
      (node (ref "R77") (pin "1") (pinfunction "1_1") (pintype "passive"))
    )
    (net (code "36") (name "/DP_HRESET") (class "Default")
      (node (ref "IC13") (pin "44") (pinfunction "HRESET_44") (pintype "passive"))
      (node (ref "R95") (pin "1") (pinfunction "1_1") (pintype "passive"))
    )
    (net (code "37") (name "/DP_I2C1_IRQ") (class "Default")
      (node (ref "IC13") (pin "29") (pinfunction "I2C1_IRQ_29") (pintype "passive"))
      (node (ref "R101") (pin "2") (pinfunction "2_2") (pintype "passive"))
    )
    (net (code "38") (name "/DP_I2C1_SCL") (class "Default")
      (node (ref "IC13") (pin "27") (pinfunction "I2C1_SCL_27") (pintype "passive"))
      (node (ref "R144") (pin "2") (pinfunction "2_2") (pintype "passive"))
      (node (ref "R189") (pin "2") (pinfunction "2_2") (pintype "passive"))
      (node (ref "R73") (pin "1") (pinfunction "1_1") (pintype "passive"))
    )
    (net (code "39") (name "/DP_I2C1_SDA") (class "Default")
      (node (ref "IC13") (pin "28") (pinfunction "I2C1_SDA_28") (pintype "passive"))
      (node (ref "R188") (pin "2") (pinfunction "2_2") (pintype "passive"))
      (node (ref "R75") (pin "1") (pinfunction "1_1") (pintype "passive"))
      (node (ref "R98") (pin "2") (pinfunction "2_2") (pintype "passive"))
    )
    (net (code "40") (name "/DP_I2C2_IRQ") (class "Default")
      (node (ref "IC13") (pin "34") (pinfunction "I2C2_IRQ_34") (pintype "passive"))
      (node (ref "R99") (pin "2") (pinfunction "2_2") (pintype "passive"))
    )
    (net (code "41") (name "/DP_I2C2_SCL") (class "Default")
      (node (ref "IC13") (pin "32") (pinfunction "I2C2_SCL_32") (pintype "passive"))
      (node (ref "J4") (pin "1") (pinfunction "1_1") (pintype "passive"))
      (node (ref "R179") (pin "2") (pinfunction "2_2") (pintype "passive"))
    )
    (net (code "42") (name "/DP_I2C2_SDA") (class "Default")
      (node (ref "IC13") (pin "33") (pinfunction "I2C2_SDA_33") (pintype "passive"))
      (node (ref "J4") (pin "2") (pinfunction "2_2") (pintype "passive"))
      (node (ref "R198") (pin "2") (pinfunction "2_2") (pintype "passive"))
    )
    (net (code "43") (name "/DP_I2C3_IRQ") (class "Default")
      (node (ref "IC13") (pin "23") (pinfunction "I2C3_IRQ_(GPIO7)_23") (pintype "passive"))
      (node (ref "R199") (pin "2") (pinfunction "2_2") (pintype "passive"))
    )
    (net (code "44") (name "/DP_I2C3_SCL") (class "Default")
      (node (ref "IC13") (pin "21") (pinfunction "I2C3_SCL_(GPIO5)_21") (pintype "passive"))
      (node (ref "R201") (pin "2") (pinfunction "2_2") (pintype "passive"))
    )
    (net (code "45") (name "/DP_I2C3_SDA") (class "Default")
      (node (ref "IC13") (pin "22") (pinfunction "I2C3_SDA_(GPIO6)_22") (pintype "passive"))
      (node (ref "R200") (pin "2") (pinfunction "2_2") (pintype "passive"))
    )
    (net (code "46") (name "/DP_I2C_EN") (class "Default")
      (node (ref "IC4") (pin "17") (pinfunction "I2C_EN_17") (pintype "passive"))
      (node (ref "R78") (pin "2") (pinfunction "2_2") (pintype "passive"))
      (node (ref "R86") (pin "1") (pinfunction "1_1") (pintype "passive"))
    )
    (net (code "47") (name "/DP_LDO_1V8") (class "Default")
      (node (ref "C132") (pin "1") (pinfunction "1_1") (pintype "passive"))
      (node (ref "IC13") (pin "35") (pinfunction "LDO_1V8_35") (pintype "passive"))
    )
    (net (code "48") (name "/DP_LDO_3V3") (class "Default")
      (node (ref "C131") (pin "1") (pinfunction "1_1") (pintype "passive"))
      (node (ref "C148") (pin "1") (pinfunction "1_1") (pintype "passive"))
      (node (ref "IC13") (pin "9") (pinfunction "LDO_3V3_9") (pintype "passive"))
      (node (ref "IC5") (pin "8") (pinfunction "VCC_8") (pintype "passive"))
      (node (ref "R101") (pin "1") (pinfunction "1_1") (pintype "passive"))
      (node (ref "R102") (pin "1") (pinfunction "1_1") (pintype "passive"))
      (node (ref "R103") (pin "1") (pinfunction "1_1") (pintype "passive"))
      (node (ref "R105") (pin "1") (pinfunction "1_1") (pintype "passive"))
      (node (ref "R112") (pin "1") (pinfunction "1_1") (pintype "passive"))
      (node (ref "R144") (pin "1") (pinfunction "1_1") (pintype "passive"))
      (node (ref "R179") (pin "1") (pinfunction "1_1") (pintype "passive"))
      (node (ref "R193") (pin "1") (pinfunction "1_1") (pintype "passive"))
      (node (ref "R194") (pin "1") (pinfunction "1_1") (pintype "passive"))
      (node (ref "R198") (pin "1") (pinfunction "1_1") (pintype "passive"))
      (node (ref "R199") (pin "1") (pinfunction "1_1") (pintype "passive"))
      (node (ref "R200") (pin "1") (pinfunction "1_1") (pintype "passive"))
      (node (ref "R201") (pin "1") (pinfunction "1_1") (pintype "passive"))
      (node (ref "R96") (pin "1") (pinfunction "1_1") (pintype "passive"))
      (node (ref "R98") (pin "1") (pinfunction "1_1") (pintype "passive"))
      (node (ref "R99") (pin "1") (pinfunction "1_1") (pintype "passive"))
      (node (ref "X5") (pin "3") (pinfunction "3_3") (pintype "passive"))
    )
    (net (code "49") (name "/DP_RX1_N") (class "Default")
      (node (ref "CO1") (pin "30") (pinfunction "B10_30") (pintype "passive"))
      (node (ref "D7") (pin "4") (pinfunction "CH3_4") (pintype "passive"))
      (node (ref "D7") (pin "7") (pinfunction "NC_7") (pintype "passive"))
      (node (ref "IC4") (pin "31") (pinfunction "RX1N_31") (pintype "passive"))
    )
    (net (code "50") (name "/DP_RX1_P") (class "Default")
      (node (ref "CO1") (pin "31") (pinfunction "B11_31") (pintype "passive"))
      (node (ref "D7") (pin "5") (pinfunction "CH4_5") (pintype "passive"))
      (node (ref "D7") (pin "6") (pinfunction "NC_6") (pintype "passive"))
      (node (ref "IC4") (pin "30") (pinfunction "RX1P_30") (pintype "passive"))
    )
    (net (code "51") (name "/DP_RX2_N") (class "Default")
      (node (ref "CO1") (pin "10") (pinfunction "A10_10") (pintype "passive"))
      (node (ref "D9") (pin "2") (pinfunction "CH2_2") (pintype "passive"))
      (node (ref "D9") (pin "9") (pinfunction "NC_9") (pintype "passive"))
      (node (ref "IC4") (pin "39") (pinfunction "RX2N_39") (pintype "passive"))
    )
    (net (code "52") (name "/DP_RX2_P") (class "Default")
      (node (ref "CO1") (pin "11") (pinfunction "A11_11") (pintype "passive"))
      (node (ref "D9") (pin "1") (pinfunction "CH1_1") (pintype "passive"))
      (node (ref "D9") (pin "10") (pinfunction "NC_10") (pintype "passive"))
      (node (ref "IC4") (pin "40") (pinfunction "RX2P_40") (pintype "passive"))
    )
    (net (code "53") (name "/DP_SBU1") (class "Default")
      (node (ref "CO1") (pin "8") (pinfunction "A8_8") (pintype "passive"))
      (node (ref "IC4") (pin "27") (pinfunction "SBU1_27") (pintype "passive"))
      (node (ref "R44") (pin "1") (pinfunction "1_1") (pintype "passive"))
    )
    (net (code "54") (name "/DP_SBU2") (class "Default")
      (node (ref "CO1") (pin "28") (pinfunction "B8_28") (pintype "passive"))
      (node (ref "IC4") (pin "26") (pinfunction "SBU2_26") (pintype "passive"))
      (node (ref "R192") (pin "1") (pinfunction "1_1") (pintype "passive"))
    )
    (net (code "55") (name "/DP_SPI_CLK") (class "Default")
      (node (ref "IC13") (pin "38") (pinfunction "SPI_CLK_(GPIO10)_38") (pintype "passive"))
      (node (ref "IC5") (pin "6") (pinfunction "SCLK_6") (pintype "passive"))
      (node (ref "X5") (pin "4") (pinfunction "4_4") (pintype "passive"))
    )
    (net (code "56") (name "/DP_SPI_CS") (class "Default")
      (node (ref "IC13") (pin "39") (pinfunction "SPI_CS_(GPIO11)_39") (pintype "passive"))
      (node (ref "IC5") (pin "1") (pinfunction "CS#_1") (pintype "passive"))
      (node (ref "R103") (pin "2") (pinfunction "2_2") (pintype "passive"))
      (node (ref "X5") (pin "1") (pinfunction "1_1") (pintype "passive"))
    )
    (net (code "57") (name "/DP_SPI_HOLD") (class "Default")
      (node (ref "IC5") (pin "7") (pinfunction "HOLD#_7") (pintype "passive"))
      (node (ref "R102") (pin "2") (pinfunction "2_2") (pintype "passive"))
    )
    (net (code "58") (name "/DP_SPI_MISO") (class "Default")
      (node (ref "IC13") (pin "36") (pinfunction "SPI_PICO_(GPIO8)_36") (pintype "passive"))
      (node (ref "IC5") (pin "2") (pinfunction "SO/SIO1_2") (pintype "passive"))
      (node (ref "R105") (pin "2") (pinfunction "2_2") (pintype "passive"))
      (node (ref "X5") (pin "6") (pinfunction "6_6") (pintype "passive"))
    )
    (net (code "59") (name "/DP_SPI_MOSI") (class "Default")
      (node (ref "IC13") (pin "37") (pinfunction "SPI_POCI_(GPIO9)_37") (pintype "passive"))
      (node (ref "IC5") (pin "5") (pinfunction "SI/SIO0_5") (pintype "passive"))
      (node (ref "R193") (pin "2") (pinfunction "2_2") (pintype "passive"))
      (node (ref "X5") (pin "2") (pinfunction "2_2") (pintype "passive"))
    )
    (net (code "60") (name "/DP_SPI_WP") (class "Default")
      (node (ref "IC5") (pin "3") (pinfunction "WP#_3") (pintype "passive"))
      (node (ref "R112") (pin "2") (pinfunction "2_2") (pintype "passive"))
    )
    (net (code "61") (name "/DP_SSEQ0") (class "Default")
      (node (ref "IC4") (pin "11") (pinfunction "SSEQ0/A0_11") (pintype "passive"))
      (node (ref "R81") (pin "2") (pinfunction "2_2") (pintype "passive"))
      (node (ref "R89") (pin "1") (pinfunction "1_1") (pintype "passive"))
    )
    (net (code "62") (name "/DP_SSEQ1") (class "Default")
      (node (ref "IC4") (pin "3") (pinfunction "SSEQ1_3") (pintype "passive"))
      (node (ref "R82") (pin "2") (pinfunction "2_2") (pintype "passive"))
      (node (ref "R90") (pin "1") (pinfunction "1_1") (pintype "passive"))
    )
    (net (code "63") (name "/DP_TX1_C_N") (class "Default")
      (node (ref "C45") (pin "2") (pinfunction "2_2") (pintype "passive"))
      (node (ref "IC4") (pin "34") (pinfunction "TX1N_34") (pintype "passive"))
    )
    (net (code "64") (name "/DP_TX1_C_P") (class "Default")
      (node (ref "C44") (pin "2") (pinfunction "2_2") (pintype "passive"))
      (node (ref "IC4") (pin "33") (pinfunction "TX1P_33") (pintype "passive"))
    )
    (net (code "65") (name "/DP_TX1_N") (class "Default")
      (node (ref "C45") (pin "1") (pinfunction "1_1") (pintype "passive"))
      (node (ref "CO1") (pin "3") (pinfunction "A3_3") (pintype "passive"))
      (node (ref "D7") (pin "1") (pinfunction "CH1_1") (pintype "passive"))
      (node (ref "D7") (pin "10") (pinfunction "NC_10") (pintype "passive"))
    )
    (net (code "66") (name "/DP_TX1_P") (class "Default")
      (node (ref "C44") (pin "1") (pinfunction "1_1") (pintype "passive"))
      (node (ref "CO1") (pin "2") (pinfunction "A2_2") (pintype "passive"))
      (node (ref "D7") (pin "2") (pinfunction "CH2_2") (pintype "passive"))
      (node (ref "D7") (pin "9") (pinfunction "NC_9") (pintype "passive"))
    )
    (net (code "67") (name "/DP_TX2_C_N") (class "Default")
      (node (ref "C42") (pin "2") (pinfunction "2_2") (pintype "passive"))
      (node (ref "IC4") (pin "36") (pinfunction "TX2N_36") (pintype "passive"))
    )
    (net (code "68") (name "/DP_TX2_C_P") (class "Default")
      (node (ref "C35") (pin "2") (pinfunction "2_2") (pintype "passive"))
      (node (ref "IC4") (pin "37") (pinfunction "TX2P_37") (pintype "passive"))
    )
    (net (code "69") (name "/DP_TX2_N") (class "Default")
      (node (ref "C42") (pin "1") (pinfunction "1_1") (pintype "passive"))
      (node (ref "CO1") (pin "23") (pinfunction "B3_23") (pintype "passive"))
      (node (ref "D9") (pin "5") (pinfunction "CH4_5") (pintype "passive"))
      (node (ref "D9") (pin "6") (pinfunction "NC_6") (pintype "passive"))
    )
    (net (code "70") (name "/DP_TX2_P") (class "Default")
      (node (ref "C35") (pin "1") (pinfunction "1_1") (pintype "passive"))
      (node (ref "CO1") (pin "22") (pinfunction "B2_22") (pintype "passive"))
      (node (ref "D9") (pin "4") (pinfunction "CH3_4") (pintype "passive"))
      (node (ref "D9") (pin "7") (pinfunction "NC_7") (pintype "passive"))
    )
    (net (code "71") (name "/DP_USB3_RX_C_N") (class "Default")
      (node (ref "C43") (pin "1") (pinfunction "1_1") (pintype "passive"))
      (node (ref "IC4") (pin "4") (pinfunction "SSRXN_4") (pintype "passive"))
    )
    (net (code "72") (name "/DP_USB3_RX_C_P") (class "Default")
      (node (ref "C36") (pin "1") (pinfunction "1_1") (pintype "passive"))
      (node (ref "IC4") (pin "5") (pinfunction "SSRXP_5") (pintype "passive"))
    )
    (net (code "73") (name "/DP_USB3_RX_N") (class "Default")
      (node (ref "C43") (pin "2") (pinfunction "2_2") (pintype "passive"))
    )
    (net (code "74") (name "/DP_USB3_RX_P") (class "Default")
      (node (ref "C36") (pin "2") (pinfunction "2_2") (pintype "passive"))
    )
    (net (code "75") (name "/DP_USB3_TX_N") (class "Default")
      (node (ref "IC4") (pin "7") (pinfunction "SSTXN_7") (pintype "passive"))
    )
    (net (code "76") (name "/DP_USB3_TX_P") (class "Default")
      (node (ref "IC4") (pin "8") (pinfunction "SSTXP_8") (pintype "passive"))
    )
    (net (code "77") (name "/DP_VBUS") (class "Default")
      (node (ref "C37") (pin "1") (pinfunction "1_1") (pintype "passive"))
      (node (ref "C38") (pin "1") (pinfunction "1_1") (pintype "passive"))
      (node (ref "C39") (pin "1") (pinfunction "1_1") (pintype "passive"))
      (node (ref "C40") (pin "1") (pinfunction "1_1") (pintype "passive"))
      (node (ref "C41") (pin "1") (pinfunction "1_1") (pintype "passive"))
      (node (ref "CO1") (pin "24") (pinfunction "B4_24") (pintype "passive"))
      (node (ref "CO1") (pin "29") (pinfunction "B9_29") (pintype "passive"))
      (node (ref "CO1") (pin "4") (pinfunction "A4_4") (pintype "passive"))
      (node (ref "CO1") (pin "9") (pinfunction "A9_9") (pintype "passive"))
      (node (ref "D24") (pin "4") (pinfunction "IN_4") (pintype "input"))
      (node (ref "D24") (pin "5") (pinfunction "IN_5") (pintype "input"))
      (node (ref "D24") (pin "6") (pinfunction "IN_6") (pintype "input"))
      (node (ref "IC13") (pin "13") (pinfunction "VBUS1_13") (pintype "passive"))
      (node (ref "IC13") (pin "14") (pinfunction "VBUS1_14") (pintype "passive"))
      (node (ref "IC13") (pin "3") (pinfunction "VBUS2_3") (pintype "passive"))
      (node (ref "IC13") (pin "4") (pinfunction "VBUS2_4") (pintype "passive"))
      (node (ref "R94") (pin "1") (pinfunction "1_1") (pintype "passive"))
    )
    (net (code "81") (name "GND") (class "Default")
      (node (ref "C130") (pin "2") (pinfunction "2_2") (pintype "passive"))
      (node (ref "C131") (pin "2") (pinfunction "2_2") (pintype "passive"))
      (node (ref "C132") (pin "2") (pinfunction "2_2") (pintype "passive"))
      (node (ref "C148") (pin "2") (pinfunction "2_2") (pintype "passive"))
      (node (ref "C159") (pin "2") (pinfunction "2_2") (pintype "passive"))
      (node (ref "C31") (pin "2") (pinfunction "2_2") (pintype "passive"))
      (node (ref "C32") (pin "2") (pinfunction "2_2") (pintype "passive"))
      (node (ref "C33") (pin "2") (pinfunction "2_2") (pintype "passive"))
      (node (ref "C34") (pin "2") (pinfunction "2_2") (pintype "passive"))
      (node (ref "C37") (pin "2") (pinfunction "2_2") (pintype "passive"))
      (node (ref "C38") (pin "2") (pinfunction "2_2") (pintype "passive"))
      (node (ref "C39") (pin "2") (pinfunction "2_2") (pintype "passive"))
      (node (ref "C40") (pin "2") (pinfunction "2_2") (pintype "passive"))
      (node (ref "C41") (pin "2") (pinfunction "2_2") (pintype "passive"))
      (node (ref "C47") (pin "2") (pinfunction "2_2") (pintype "passive"))
      (node (ref "C48") (pin "2") (pinfunction "2_2") (pintype "passive"))
      (node (ref "C91") (pin "2") (pinfunction "2_2") (pintype "passive"))
      (node (ref "CO1") (pin "1") (pinfunction "A1_1") (pintype "passive"))
      (node (ref "CO1") (pin "12") (pinfunction "A12_12") (pintype "passive"))
      (node (ref "CO1") (pin "21") (pinfunction "B1_21") (pintype "passive"))
      (node (ref "CO1") (pin "32") (pinfunction "B12_32") (pintype "passive"))
      (node (ref "CO1") (pin "SH") (pinfunction "SH_SH") (pintype "power_in"))
      (node (ref "D17") (pin "1") (pinfunction "Cathode_1") (pintype "passive"))
      (node (ref "D24") (pin "1") (pinfunction "GND_1") (pintype "power_in"))
      (node (ref "D24") (pin "2") (pinfunction "GND_2") (pintype "power_in"))
      (node (ref "D24") (pin "3") (pinfunction "GND_3") (pintype "power_in"))
      (node (ref "D24") (pin "7") (pinfunction "GND_7") (pintype "power_in"))
      (node (ref "D6") (pin "3") (pinfunction "GND_3") (pintype "power_in"))
      (node (ref "D7") (pin "3") (pinfunction "GND_3") (pintype "passive"))
      (node (ref "D7") (pin "8") (pinfunction "GND_8") (pintype "passive"))
      (node (ref "D9") (pin "3") (pinfunction "GND_3") (pintype "passive"))
      (node (ref "D9") (pin "8") (pinfunction "GND_8") (pintype "passive"))
      (node (ref "IC13") (pin "20") (pinfunction "GND_20") (pintype "passive"))
      (node (ref "IC13") (pin "45") (pinfunction "GND_45") (pintype "passive"))
      (node (ref "IC13") (pin "46") (pinfunction "GND_46") (pintype "passive"))
      (node (ref "IC13") (pin "47") (pinfunction "GND_47") (pintype "passive"))
      (node (ref "IC13") (pin "51") (pinfunction "GND_51") (pintype "passive"))
      (node (ref "IC13") (pin "59") (pinfunction "GND_59") (pintype "passive"))
      (node (ref "IC4") (pin "41") (pinfunction "EP_41") (pintype "passive"))
      (node (ref "IC5") (pin "4") (pinfunction "GND_4") (pintype "passive"))
      (node (ref "J4") (pin "3") (pinfunction "3_3") (pintype "passive"))
      (node (ref "R100") (pin "2") (pinfunction "2_2") (pintype "passive"))
      (node (ref "R192") (pin "2") (pinfunction "2_2") (pintype "passive"))
      (node (ref "R195") (pin "2") (pinfunction "2_2") (pintype "passive"))
      (node (ref "R44") (pin "2") (pinfunction "2_2") (pintype "passive"))
      (node (ref "R86") (pin "2") (pinfunction "2_2") (pintype "passive"))
      (node (ref "R87") (pin "2") (pinfunction "2_2") (pintype "passive"))
      (node (ref "R88") (pin "2") (pinfunction "2_2") (pintype "passive"))
      (node (ref "R89") (pin "2") (pinfunction "2_2") (pintype "passive"))
      (node (ref "R90") (pin "2") (pinfunction "2_2") (pintype "passive"))
      (node (ref "R91") (pin "2") (pinfunction "2_2") (pintype "passive"))
      (node (ref "R92") (pin "2") (pinfunction "2_2") (pintype "passive"))
      (node (ref "R93") (pin "2") (pinfunction "2_2") (pintype "passive"))
      (node (ref "R95") (pin "2") (pinfunction "2_2") (pintype "passive"))
      (node (ref "X5") (pin "5") (pinfunction "5_5") (pintype "passive"))
    )
    (net (code "82") (name "Net-(D17-Anode)") (class "Default")
      (node (ref "D17") (pin "2") (pinfunction "Anode_2") (pintype "passive"))
      (node (ref "R94") (pin "2") (pinfunction "2_2") (pintype "passive"))
    )
    (net (code "83") (name "Net-(IC13-C_USB_N_(GPIO19))") (class "Default")
      (node (ref "IC13") (pin "53") (pinfunction "C_USB_N_(GPIO19)_53") (pintype "passive"))
      (node (ref "R185") (pin "1") (pinfunction "1_1") (pintype "passive"))
    )
    (net (code "84") (name "Net-(IC13-C_USB_P_(GPIO18))") (class "Default")
      (node (ref "IC13") (pin "50") (pinfunction "C_USB_P_(GPIO18)_50") (pintype "passive"))
      (node (ref "R184") (pin "1") (pinfunction "1_1") (pintype "passive"))
    )
    (net (code "85") (name "Net-(IC13-DRAIN1-Pad15)") (class "Default")
      (node (ref "IC13") (pin "15") (pinfunction "DRAIN1_15") (pintype "passive"))
      (node (ref "IC13") (pin "19") (pinfunction "DRAIN1_19") (pintype "passive"))
      (node (ref "IC13") (pin "58") (pinfunction "DRAIN1_58") (pintype "passive"))
      (node (ref "IC13") (pin "8") (pinfunction "DRAIN1_8") (pintype "passive"))
    )
    (net (code "86") (name "Net-(IC13-DRAIN2-Pad52)") (class "Default")
      (node (ref "IC13") (pin "52") (pinfunction "DRAIN2_52") (pintype "passive"))
      (node (ref "IC13") (pin "56") (pinfunction "DRAIN2_56") (pintype "passive"))
      (node (ref "IC13") (pin "57") (pinfunction "DRAIN2_57") (pintype "passive"))
      (node (ref "IC13") (pin "7") (pinfunction "DRAIN2_7") (pintype "passive"))
    )
    (net (code "87") (name "Net-(IC13-PP_HV1-Pad11)") (class "Default")
      (node (ref "IC13") (pin "11") (pinfunction "PP_HV1_11") (pintype "passive"))
      (node (ref "IC13") (pin "12") (pinfunction "PP_HV1_12") (pintype "passive"))
      (node (ref "R196") (pin "2") (pinfunction "2_2") (pintype "passive"))
    )
    (net (code "88") (name "unconnected-(IC13-GPIO4-Pad31)") (class "Default")
      (node (ref "IC13") (pin "31") (pinfunction "GPIO4_31") (pintype "passive"))
    )
    (net (code "89") (name "unconnected-(IC13-GPIO12-Pad40)") (class "Default")
      (node (ref "IC13") (pin "40") (pinfunction "GPIO12_40") (pintype "passive"))
    )
    (net (code "90") (name "unconnected-(IC13-GPIO13-Pad41)") (class "Default")
      (node (ref "IC13") (pin "41") (pinfunction "GPIO13_41") (pintype "passive"))
    )
    (net (code "91") (name "unconnected-(IC13-GPIO14_(PWM)-Pad42)") (class "Default")
      (node (ref "IC13") (pin "42") (pinfunction "GPIO14_(PWM)_42") (pintype "passive"))
    )
    (net (code "92") (name "unconnected-(IC13-GPIO15_(PWM)-Pad43)") (class "Default")
      (node (ref "IC13") (pin "43") (pinfunction "GPIO15_(PWM)_43") (pintype "passive"))
    )
    (net (code "93") (name "unconnected-(IC13-GPIO16_(PEXT1)-Pad48)") (class "Default")
      (node (ref "IC13") (pin "48") (pinfunction "GPIO16_(PEXT1)_48") (pintype "passive"))
    )
    (net (code "94") (name "unconnected-(IC13-GPIO17_(PEXT2)-Pad49)") (class "Default")
      (node (ref "IC13") (pin "49") (pinfunction "GPIO17_(PEXT2)_49") (pintype "passive"))
    )
    (net (code "95") (name "unconnected-(IC13-GPIO20-Pad54)") (class "Default")
      (node (ref "IC13") (pin "54") (pinfunction "GPIO20_54") (pintype "passive"))
    )
    (net (code "96") (name "unconnected-(IC13-GPIO21-Pad55)") (class "Default")
      (node (ref "IC13") (pin "55") (pinfunction "GPIO21_55") (pintype "passive"))
    )
  )
)
